# I2C_extender_0.net
KiCad netlist of a schematic drawn in Altium Designer
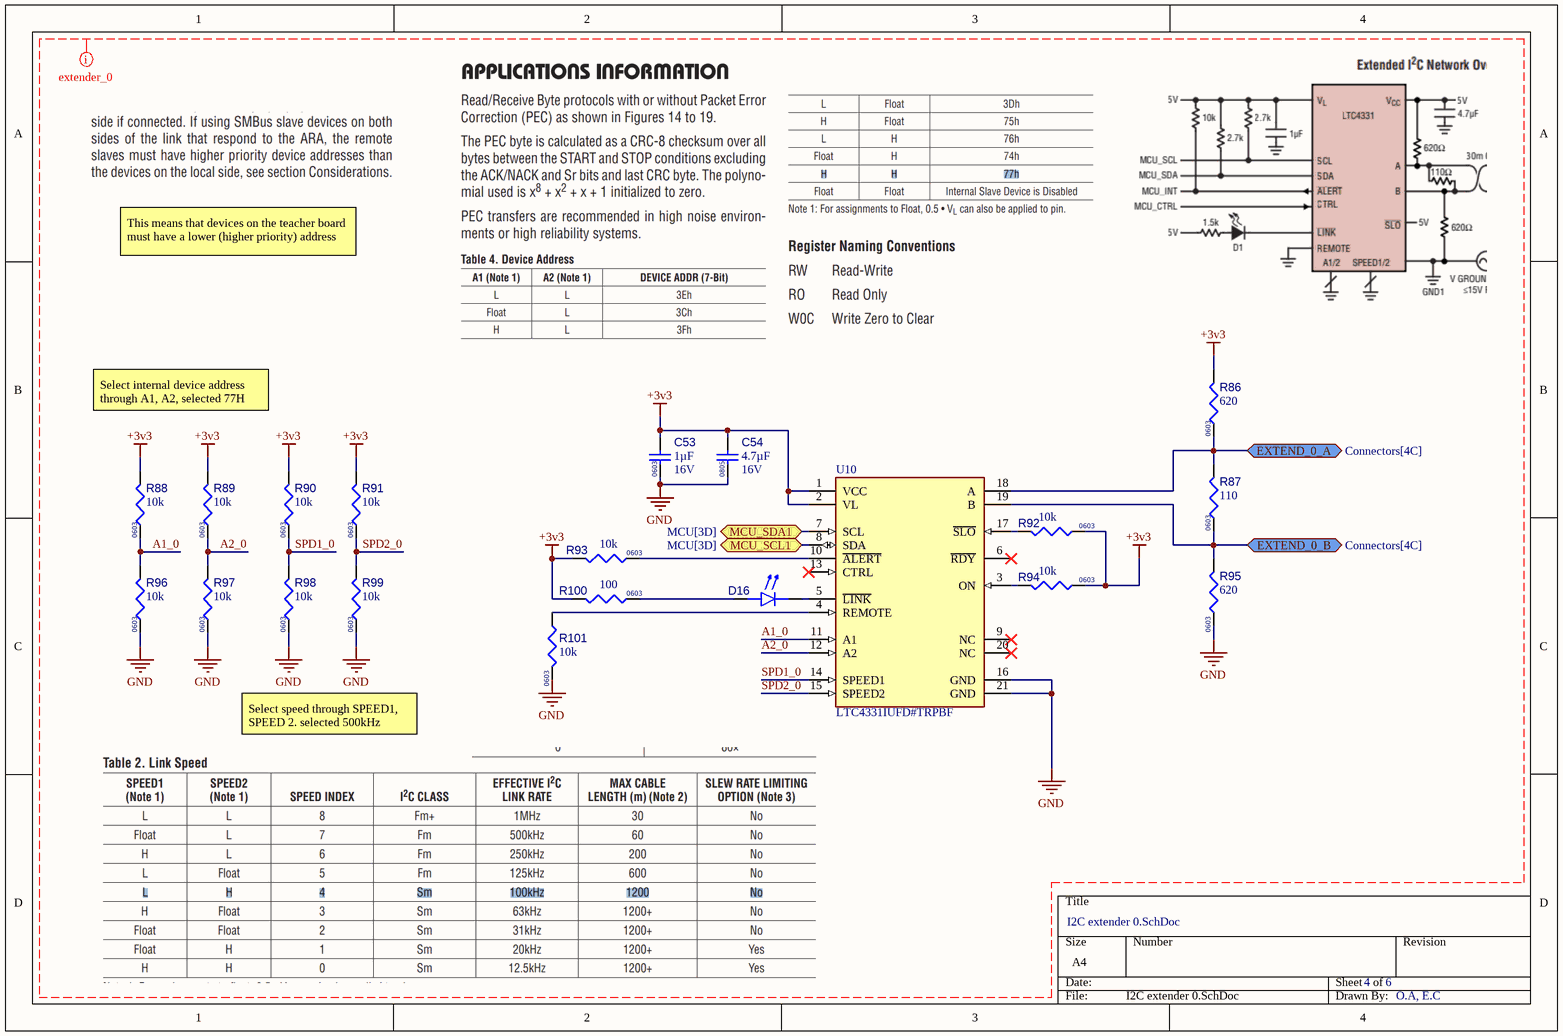
[diagram p0: I2C extender 0.SchDoc]

(export (version "E")
  (design (tool "Eeschema 10.0.6"))
  (components
    (comp (ref "C53")
      (value "1µF")
      (footprint "CAPC1608X90X35NL15T15")
      (description "Chip Capacitor, 1 uF, +/- 10%, 16 V, 0603 (1608 Metric)")
      (fields
        (field (name "CASE/PACKAGE") "0603")
        (field (name "VOLTAGE RATING") "16V")
        (field (name "TOLERANCE") "10%")
        (field (name "Comment") "Capacitor 1uF +/- 10% 16V 0603")
      )
      (libsource (lib "hawaiirobotics") (part "CAP-NP-2"))
    )
    (comp (ref "C54")
      (value "4.7µF")
      (footprint "CL21A475KOFNNNE-Footprint-1")
      (fields
        (field (name "CASE/PACKAGE") "0805")
        (field (name "RATED DC VOLTAGE (URDC)") "16V")
        (field (name "Comment") "CL21A475KOFNNNE")
      )
      (libsource (lib "hawaiirobotics") (part "CAP-NP-2"))
    )
    (comp (ref "D16")
      (value "150060YS75000")
      (footprint "WL-SMCW_0603_150060xx75000")
      (description "Single Color LED, Yellow, Water Clear, 1.1mm")
      (libsource (lib "hawaiirobotics") (part "DIODE-LED-2"))
    )
    (comp (ref "R86")
      (value "620")
      (footprint "RC0603JR-0720KL-Footprint-1")
      (fields
        (field (name "POWER") "100mW")
        (field (name "CASE/PACKAGE") "0603")
        (field (name "TOLERANCE") "1%")
        (field (name "Comment") "RC0603FR-07620RL")
      )
      (libsource (lib "hawaiirobotics") (part "RES-2"))
    )
    (comp (ref "R87")
      (value "110")
      (footprint "RC0603JR-0720KL-Footprint-1")
      (fields
        (field (name "TOLERANCE") "1%")
        (field (name "POWER") "100mW")
        (field (name "CASE/PACKAGE") "0603")
        (field (name "Comment") "RC0603FR-07110RL")
      )
      (libsource (lib "hawaiirobotics") (part "RES-2"))
    )
    (comp (ref "R88")
      (value "10k")
      (footprint "RESC1608X55X25NL10T15")
      (description "Chip Resistor, 10 KOhm, +/- 1%, 01 W, -55 to 155 degC, 0603 (1608 Metric)")
      (fields
        (field (name "CASE/PACKAGE") "0603")
        (field (name "POWER") "100mW")
        (field (name "TOLERANCE") "1%")
      )
      (libsource (lib "hawaiirobotics") (part "RES-2"))
    )
    (comp (ref "R89")
      (value "10k")
      (footprint "RESC1608X55X25NL10T15")
      (description "Chip Resistor, 10 KOhm, +/- 1%, 01 W, -55 to 155 degC, 0603 (1608 Metric)")
      (fields
        (field (name "CASE/PACKAGE") "0603")
        (field (name "POWER") "100mW")
        (field (name "TOLERANCE") "1%")
      )
      (libsource (lib "hawaiirobotics") (part "RES-2"))
    )
    (comp (ref "R90")
      (value "10k")
      (footprint "RESC1608X55X25NL10T15")
      (description "Chip Resistor, 10 KOhm, +/- 1%, 01 W, -55 to 155 degC, 0603 (1608 Metric)")
      (fields
        (field (name "CASE/PACKAGE") "0603")
        (field (name "POWER") "100mW")
        (field (name "TOLERANCE") "1%")
      )
      (libsource (lib "hawaiirobotics") (part "RES-2"))
    )
    (comp (ref "R91")
      (value "10k")
      (footprint "RESC1608X55X25NL10T15")
      (description "Chip Resistor, 10 KOhm, +/- 1%, 01 W, -55 to 155 degC, 0603 (1608 Metric)")
      (fields
        (field (name "CASE/PACKAGE") "0603")
        (field (name "POWER") "100mW")
        (field (name "TOLERANCE") "1%")
      )
      (libsource (lib "hawaiirobotics") (part "RES-2"))
    )
    (comp (ref "R92")
      (value "10k")
      (footprint "RESC1608X55X25NL10T15")
      (description "Chip Resistor, 10 KOhm, +/- 1%, 01 W, -55 to 155 degC, 0603 (1608 Metric)")
      (fields
        (field (name "CASE/PACKAGE") "0603")
        (field (name "POWER") "100mW")
        (field (name "TOLERANCE") "1%")
      )
      (libsource (lib "hawaiirobotics") (part "RES-2"))
    )
    (comp (ref "R93")
      (value "10k")
      (footprint "RESC1608X55X25NL10T15")
      (description "Chip Resistor, 10 KOhm, +/- 1%, 01 W, -55 to 155 degC, 0603 (1608 Metric)")
      (fields
        (field (name "CASE/PACKAGE") "0603")
        (field (name "POWER") "100mW")
        (field (name "TOLERANCE") "1%")
      )
      (libsource (lib "hawaiirobotics") (part "RES-2"))
    )
    (comp (ref "R94")
      (value "10k")
      (footprint "RESC1608X55X25NL10T15")
      (description "Chip Resistor, 10 KOhm, +/- 1%, 01 W, -55 to 155 degC, 0603 (1608 Metric)")
      (fields
        (field (name "CASE/PACKAGE") "0603")
        (field (name "POWER") "100mW")
        (field (name "TOLERANCE") "1%")
      )
      (libsource (lib "hawaiirobotics") (part "RES-2"))
    )
    (comp (ref "R95")
      (value "620")
      (footprint "RC0603JR-0720KL-Footprint-1")
      (fields
        (field (name "POWER") "100mW")
        (field (name "CASE/PACKAGE") "0603")
        (field (name "TOLERANCE") "1%")
        (field (name "Comment") "RC0603FR-07620RL")
      )
      (libsource (lib "hawaiirobotics") (part "RES-2"))
    )
    (comp (ref "R96")
      (value "10k")
      (footprint "RESC1608X55X25NL10T15")
      (description "Chip Resistor, 10 KOhm, +/- 1%, 01 W, -55 to 155 degC, 0603 (1608 Metric)")
      (fields
        (field (name "CASE/PACKAGE") "0603")
        (field (name "POWER") "100mW")
        (field (name "TOLERANCE") "1%")
      )
      (libsource (lib "hawaiirobotics") (part "RES-2"))
    )
    (comp (ref "R97")
      (value "10k")
      (footprint "RESC1608X55X25NL10T15")
      (description "Chip Resistor, 10 KOhm, +/- 1%, 01 W, -55 to 155 degC, 0603 (1608 Metric)")
      (fields
        (field (name "CASE/PACKAGE") "0603")
        (field (name "POWER") "100mW")
        (field (name "TOLERANCE") "1%")
      )
      (libsource (lib "hawaiirobotics") (part "RES-2"))
    )
    (comp (ref "R98")
      (value "10k")
      (footprint "RESC1608X55X25NL10T15")
      (description "Chip Resistor, 10 KOhm, +/- 1%, 01 W, -55 to 155 degC, 0603 (1608 Metric)")
      (fields
        (field (name "CASE/PACKAGE") "0603")
        (field (name "POWER") "100mW")
        (field (name "TOLERANCE") "1%")
      )
      (libsource (lib "hawaiirobotics") (part "RES-2"))
    )
    (comp (ref "R99")
      (value "10k")
      (footprint "RESC1608X55X25NL10T15")
      (description "Chip Resistor, 10 KOhm, +/- 1%, 01 W, -55 to 155 degC, 0603 (1608 Metric)")
      (fields
        (field (name "CASE/PACKAGE") "0603")
        (field (name "POWER") "100mW")
        (field (name "TOLERANCE") "1%")
      )
      (libsource (lib "hawaiirobotics") (part "RES-2"))
    )
    (comp (ref "R100")
      (value "100")
      (footprint "RC0603JR-0720KL-Footprint-1")
      (fields
        (field (name "TOLERANCE") "1%")
        (field (name "CASE/PACKAGE") "0603")
        (field (name "POWER") "100mW")
        (field (name "Comment") "RC0603FR-07100RL")
      )
      (libsource (lib "hawaiirobotics") (part "RES-2"))
    )
    (comp (ref "R101")
      (value "10k")
      (footprint "RESC1608X55X25NL10T15")
      (description "Chip Resistor, 10 KOhm, +/- 1%, 01 W, -55 to 155 degC, 0603 (1608 Metric)")
      (fields
        (field (name "CASE/PACKAGE") "0603")
        (field (name "POWER") "100mW")
        (field (name "TOLERANCE") "1%")
      )
      (libsource (lib "hawaiirobotics") (part "RES-2"))
    )
    (comp (ref "U10")
      (value "LTC4331IUFD#TRPBF")
      (footprint "FP-UFD-20-05-08-1711-IPC_C")
      (description "Interface Circuit, CMOS, PQCC20")
      (libsource (lib "hawaiirobotics") (part "90934f5fbb90c4d29cf3ee1665de234"))
    )
  )
  (nets
    (net (code "1") (name "+3v3") (class "Default")
      (node (ref "C53") (pin "2") (pinfunction "2_2") (pintype "passive"))
      (node (ref "C54") (pin "2") (pinfunction "2_2") (pintype "passive"))
      (node (ref "R100") (pin "2") (pinfunction "2_2") (pintype "passive"))
      (node (ref "R86") (pin "2") (pinfunction "2_2") (pintype "passive"))
      (node (ref "R88") (pin "2") (pinfunction "2_2") (pintype "passive"))
      (node (ref "R89") (pin "2") (pinfunction "2_2") (pintype "passive"))
      (node (ref "R90") (pin "2") (pinfunction "2_2") (pintype "passive"))
      (node (ref "R91") (pin "2") (pinfunction "2_2") (pintype "passive"))
      (node (ref "R92") (pin "1") (pinfunction "1_1") (pintype "passive"))
      (node (ref "R93") (pin "1") (pinfunction "1_1") (pintype "passive"))
      (node (ref "R94") (pin "1") (pinfunction "1_1") (pintype "passive"))
      (node (ref "U10") (pin "1") (pinfunction "VCC_1") (pintype "power_in"))
      (node (ref "U10") (pin "2") (pinfunction "VL_2") (pintype "power_in"))
    )
    (net (code "2") (name "/A1_0") (class "Default")
      (node (ref "R88") (pin "1") (pinfunction "1_1") (pintype "passive"))
      (node (ref "R96") (pin "2") (pinfunction "2_2") (pintype "passive"))
      (node (ref "U10") (pin "11") (pinfunction "A1_11") (pintype "input"))
    )
    (net (code "3") (name "/A2_0") (class "Default")
      (node (ref "R89") (pin "1") (pinfunction "1_1") (pintype "passive"))
      (node (ref "R97") (pin "2") (pinfunction "2_2") (pintype "passive"))
      (node (ref "U10") (pin "12") (pinfunction "A2_12") (pintype "input"))
    )
    (net (code "4") (name "/EXTEND_0_A") (class "Default")
      (node (ref "R86") (pin "1") (pinfunction "1_1") (pintype "passive"))
      (node (ref "R87") (pin "2") (pinfunction "2_2") (pintype "passive"))
      (node (ref "U10") (pin "18") (pinfunction "A_18") (pintype "tri_state"))
    )
    (net (code "5") (name "/EXTEND_0_B") (class "Default")
      (node (ref "R87") (pin "1") (pinfunction "1_1") (pintype "passive"))
      (node (ref "R95") (pin "2") (pinfunction "2_2") (pintype "passive"))
      (node (ref "U10") (pin "19") (pinfunction "B_19") (pintype "tri_state"))
    )
    (net (code "6") (name "/MCU_SCL1") (class "Default")
      (node (ref "U10") (pin "8") (pinfunction "SDA_8") (pintype "bidirectional"))
    )
    (net (code "7") (name "/MCU_SDA1") (class "Default")
      (node (ref "U10") (pin "7") (pinfunction "SCL_7") (pintype "input"))
    )
    (net (code "8") (name "/SPD1_0") (class "Default")
      (node (ref "R90") (pin "1") (pinfunction "1_1") (pintype "passive"))
      (node (ref "R98") (pin "2") (pinfunction "2_2") (pintype "passive"))
      (node (ref "U10") (pin "14") (pinfunction "SPEED1_14") (pintype "input"))
    )
    (net (code "9") (name "/SPD2_0") (class "Default")
      (node (ref "R91") (pin "1") (pinfunction "1_1") (pintype "passive"))
      (node (ref "R99") (pin "2") (pinfunction "2_2") (pintype "passive"))
      (node (ref "U10") (pin "15") (pinfunction "SPEED2_15") (pintype "input"))
    )
    (net (code "10") (name "GND") (class "Default")
      (node (ref "C53") (pin "1") (pinfunction "1_1") (pintype "passive"))
      (node (ref "C54") (pin "1") (pinfunction "1_1") (pintype "passive"))
      (node (ref "R101") (pin "1") (pinfunction "1_1") (pintype "passive"))
      (node (ref "R95") (pin "1") (pinfunction "1_1") (pintype "passive"))
      (node (ref "R96") (pin "1") (pinfunction "1_1") (pintype "passive"))
      (node (ref "R97") (pin "1") (pinfunction "1_1") (pintype "passive"))
      (node (ref "R98") (pin "1") (pinfunction "1_1") (pintype "passive"))
      (node (ref "R99") (pin "1") (pinfunction "1_1") (pintype "passive"))
      (node (ref "U10") (pin "16") (pinfunction "GND_16") (pintype "power_in"))
      (node (ref "U10") (pin "21") (pinfunction "GND_21") (pintype "power_in"))
    )
    (net (code "11") (name "Net-(D16-A)") (class "Default")
      (node (ref "D16") (pin "2") (pinfunction "A_2") (pintype "passive"))
      (node (ref "R100") (pin "1") (pinfunction "1_1") (pintype "passive"))
    )
    (net (code "12") (name "Net-(D16-K)") (class "Default")
      (node (ref "D16") (pin "1") (pinfunction "K_1") (pintype "passive"))
      (node (ref "U10") (pin "5") (pinfunction "~{LINK}_5") (pintype "open_collector"))
    )
    (net (code "13") (name "Net-(U10-ON)") (class "Default")
      (node (ref "R94") (pin "2") (pinfunction "2_2") (pintype "passive"))
      (node (ref "U10") (pin "3") (pinfunction "ON_3") (pintype "input"))
    )
    (net (code "14") (name "Net-(U10-REMOTE)") (class "Default")
      (node (ref "R101") (pin "2") (pinfunction "2_2") (pintype "passive"))
      (node (ref "U10") (pin "4") (pinfunction "REMOTE_4") (pintype "input"))
    )
    (net (code "15") (name "Net-(U10-~{ALERT})") (class "Default")
      (node (ref "R93") (pin "2") (pinfunction "2_2") (pintype "passive"))
      (node (ref "U10") (pin "10") (pinfunction "~{ALERT}_10") (pintype "open_collector"))
    )
    (net (code "16") (name "Net-(U10-~{SLO})") (class "Default")
      (node (ref "R92") (pin "2") (pinfunction "2_2") (pintype "passive"))
      (node (ref "U10") (pin "17") (pinfunction "~{SLO}_17") (pintype "input"))
    )
    (net (code "17") (name "unconnected-(U10-CTRL-Pad13)") (class "Default")
      (node (ref "U10") (pin "13") (pinfunction "CTRL_13") (pintype "input+no_connect"))
    )
    (net (code "18") (name "unconnected-(U10-NC-Pad9)") (class "Default")
      (node (ref "U10") (pin "9") (pinfunction "NC_9") (pintype "passive+no_connect"))
    )
    (net (code "19") (name "unconnected-(U10-NC-Pad20)") (class "Default")
      (node (ref "U10") (pin "20") (pinfunction "NC_20") (pintype "passive+no_connect"))
    )
    (net (code "20") (name "unconnected-(U10-~{RDY}-Pad6)") (class "Default")
      (node (ref "U10") (pin "6") (pinfunction "~{RDY}_6") (pintype "open_collector+no_connect"))
    )
  )
)
